# 2021_Deployment_REVB.net
KiCad netlist of a schematic drawn in EAGLE
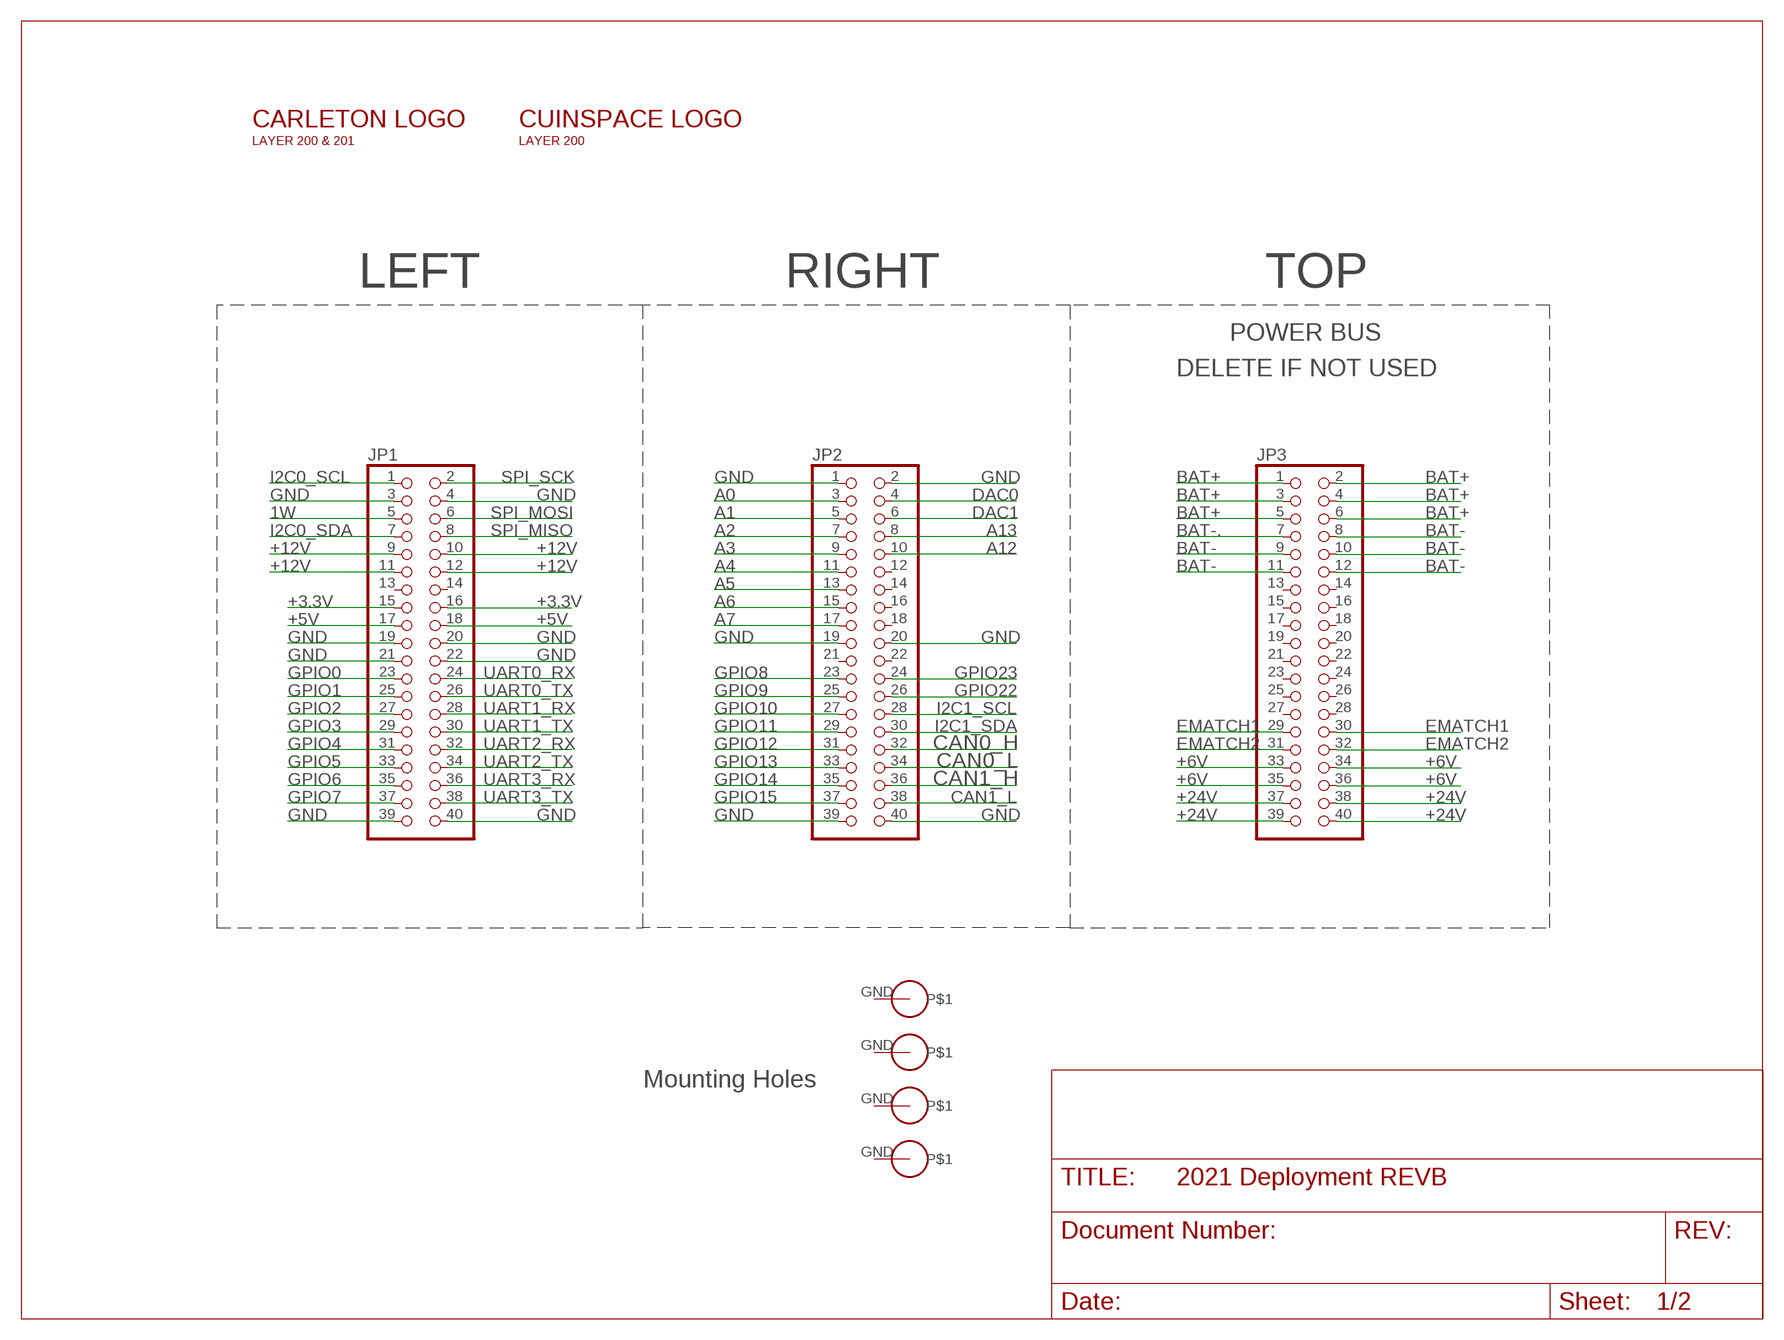
[diagram p0: schematic, sheet 1]
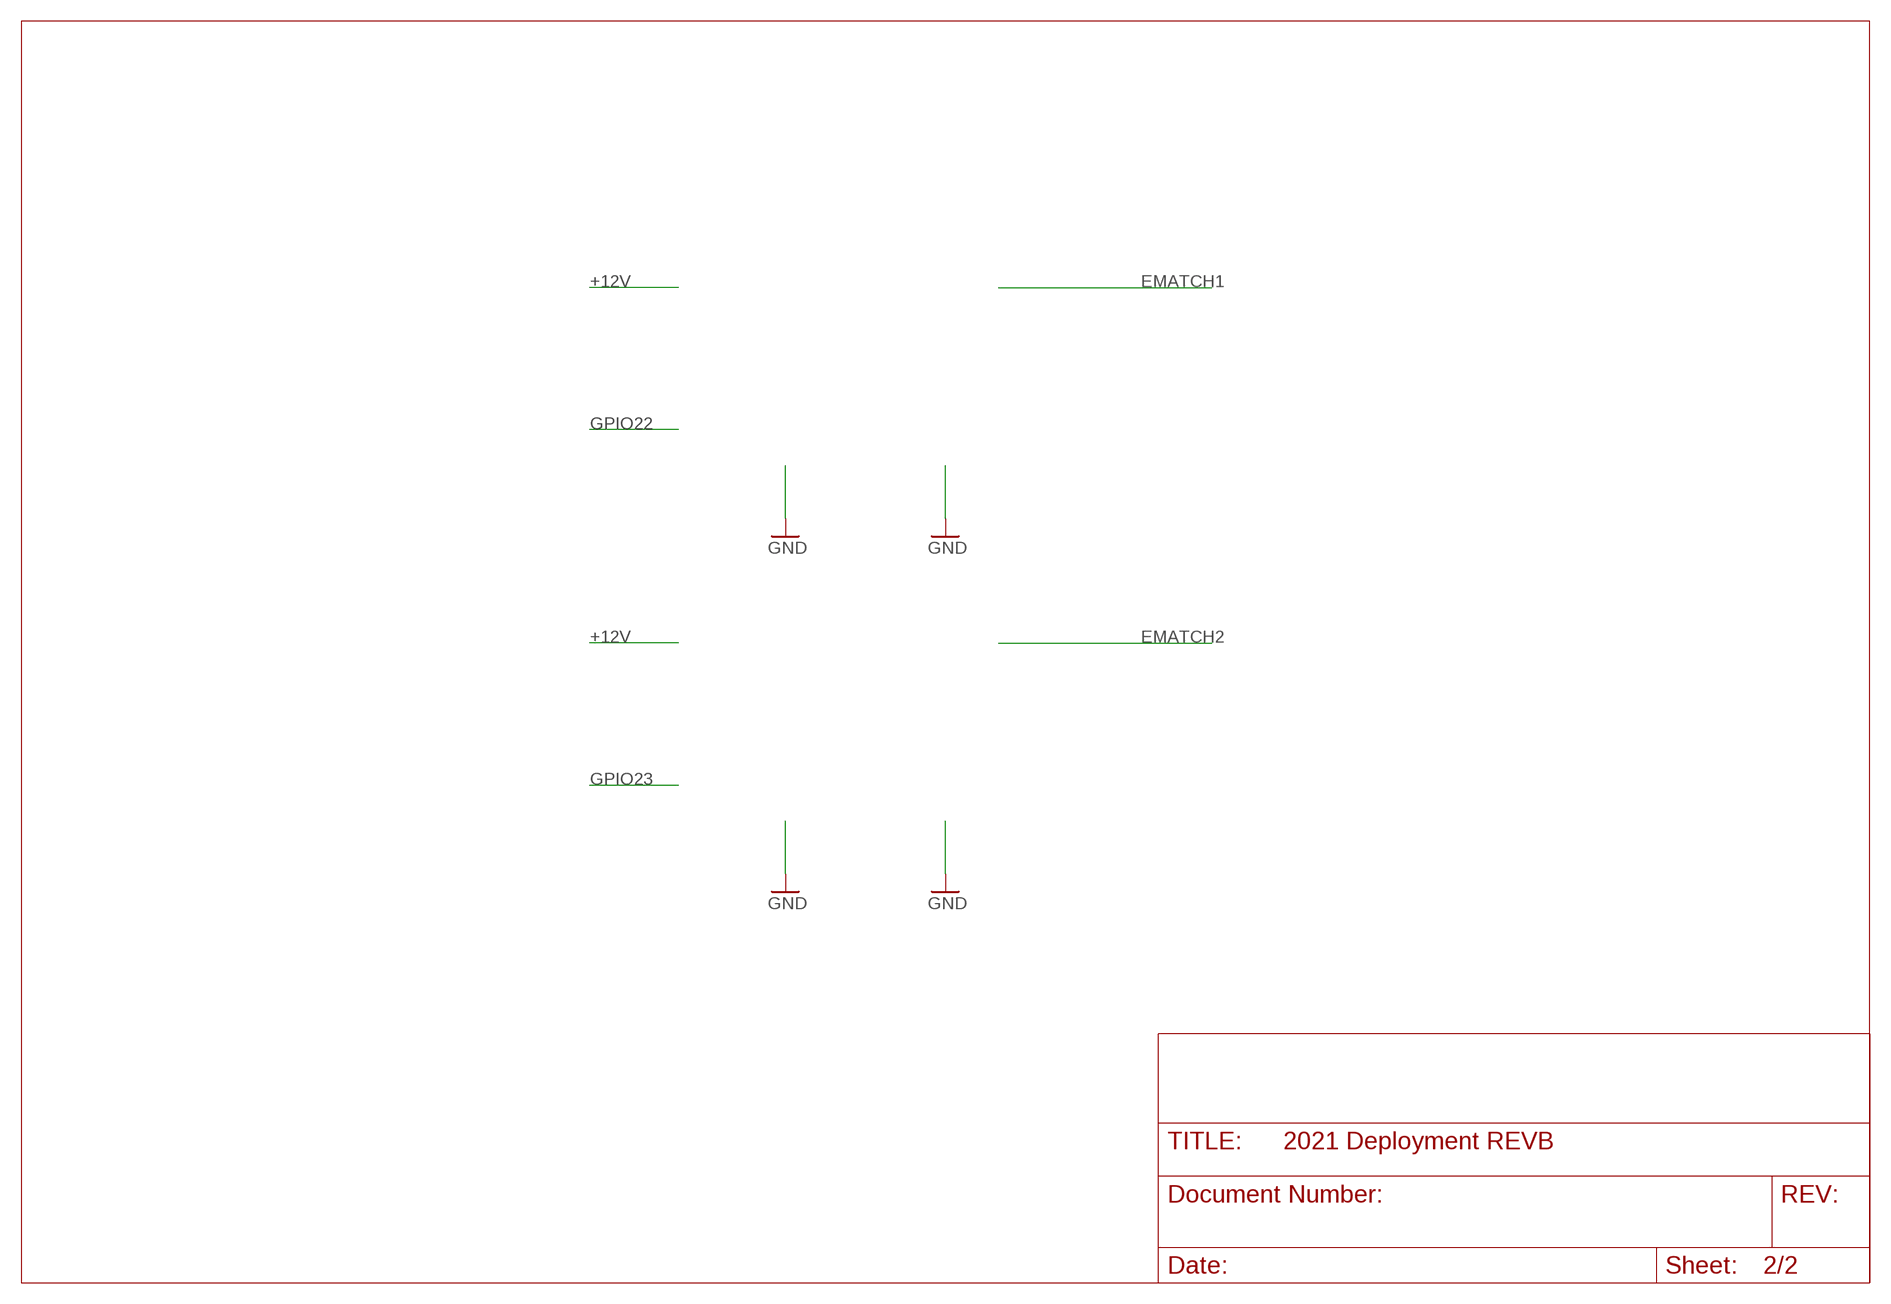
[diagram p1: schematic, sheet 2]

(export (version "E")
  (design (tool "Eeschema 10.0.6"))
  (components
    (comp (ref "$$U$1")
      (value "PS/104-MOUNTING-HOLE")
      (footprint "eagle-import:PC_104-MOUNTING-HOLE")
      (libsource (lib "eagle-import") (part "PS/104-MOUNTING-HOLE"))
    )
    (comp (ref "JP1")
      (value "PINHD-2X20")
      (footprint "eagle-import:2X20")
      (libsource (lib "eagle-import") (part "PINHD-2X20"))
    )
    (comp (ref "JP2")
      (value "PINHD-2X20")
      (footprint "eagle-import:2X20")
      (libsource (lib "eagle-import") (part "PINHD-2X20"))
    )
    (comp (ref "JP3")
      (value "PINHD-2X20")
      (footprint "eagle-import:2X20")
      (libsource (lib "eagle-import") (part "PINHD-2X20"))
    )
    (comp (ref "U$1")
      (value "PS/104-MOUNTING-HOLE")
      (footprint "eagle-import:PC_104-MOUNTING-HOLE")
      (libsource (lib "eagle-import") (part "PS/104-MOUNTING-HOLE"))
    )
    (comp (ref "U$2")
      (value "PS/104-MOUNTING-HOLE")
      (footprint "eagle-import:PC_104-MOUNTING-HOLE")
      (libsource (lib "eagle-import") (part "PS/104-MOUNTING-HOLE"))
    )
    (comp (ref "U$3")
      (value "PS/104-MOUNTING-HOLE")
      (footprint "eagle-import:PC_104-MOUNTING-HOLE")
      (libsource (lib "eagle-import") (part "PS/104-MOUNTING-HOLE"))
    )
    (comp (ref "U$4")
      (value "CARLETON3CM")
      (footprint "eagle-import:CARLETONU_3CM")
      (libsource (lib "eagle-import") (part "CARLETON3CM"))
    )
    (comp (ref "U$6")
      (value "INSPACE3CM_L")
      (footprint "eagle-import:INSPACE_3CM_LETTERS")
      (libsource (lib "eagle-import") (part "INSPACE3CM_L"))
    )
  )
  (nets
    (net (code "1") (name "+3.3V") (class "Default")
      (node (ref "JP1") (pin "15") (pinfunction "15_15") (pintype "passive"))
      (node (ref "JP1") (pin "16") (pinfunction "16_16") (pintype "passive"))
    )
    (net (code "2") (name "+5V") (class "Default")
      (node (ref "JP1") (pin "17") (pinfunction "17_17") (pintype "passive"))
      (node (ref "JP1") (pin "18") (pinfunction "18_18") (pintype "passive"))
    )
    (net (code "3") (name "+6V") (class "Default")
      (node (ref "JP3") (pin "33") (pinfunction "33_33") (pintype "passive"))
      (node (ref "JP3") (pin "34") (pinfunction "34_34") (pintype "passive"))
      (node (ref "JP3") (pin "35") (pinfunction "35_35") (pintype "passive"))
      (node (ref "JP3") (pin "36") (pinfunction "36_36") (pintype "passive"))
    )
    (net (code "4") (name "+12V") (class "Default")
      (node (ref "JP1") (pin "10") (pinfunction "10_10") (pintype "passive"))
      (node (ref "JP1") (pin "11") (pinfunction "11_11") (pintype "passive"))
      (node (ref "JP1") (pin "12") (pinfunction "12_12") (pintype "passive"))
      (node (ref "JP1") (pin "9") (pinfunction "9_9") (pintype "passive"))
    )
    (net (code "5") (name "+24V") (class "Default")
      (node (ref "JP3") (pin "37") (pinfunction "37_37") (pintype "passive"))
      (node (ref "JP3") (pin "38") (pinfunction "38_38") (pintype "passive"))
      (node (ref "JP3") (pin "39") (pinfunction "39_39") (pintype "passive"))
      (node (ref "JP3") (pin "40") (pinfunction "40_40") (pintype "passive"))
    )
    (net (code "6") (name "1W") (class "Default")
      (node (ref "JP1") (pin "5") (pinfunction "5_5") (pintype "passive"))
    )
    (net (code "7") (name "A0") (class "Default")
      (node (ref "JP2") (pin "3") (pinfunction "3_3") (pintype "passive"))
    )
    (net (code "8") (name "A1") (class "Default")
      (node (ref "JP2") (pin "5") (pinfunction "5_5") (pintype "passive"))
    )
    (net (code "9") (name "A2") (class "Default")
      (node (ref "JP2") (pin "7") (pinfunction "7_7") (pintype "passive"))
    )
    (net (code "10") (name "A3") (class "Default")
      (node (ref "JP2") (pin "9") (pinfunction "9_9") (pintype "passive"))
    )
    (net (code "11") (name "A4") (class "Default")
      (node (ref "JP2") (pin "11") (pinfunction "11_11") (pintype "passive"))
    )
    (net (code "12") (name "A5") (class "Default")
      (node (ref "JP2") (pin "13") (pinfunction "13_13") (pintype "passive"))
    )
    (net (code "13") (name "A6") (class "Default")
      (node (ref "JP2") (pin "15") (pinfunction "15_15") (pintype "passive"))
    )
    (net (code "14") (name "A7") (class "Default")
      (node (ref "JP2") (pin "17") (pinfunction "17_17") (pintype "passive"))
    )
    (net (code "15") (name "A12") (class "Default")
      (node (ref "JP2") (pin "10") (pinfunction "10_10") (pintype "passive"))
    )
    (net (code "16") (name "A13") (class "Default")
      (node (ref "JP2") (pin "8") (pinfunction "8_8") (pintype "passive"))
    )
    (net (code "17") (name "BAT+") (class "Default")
      (node (ref "JP3") (pin "1") (pinfunction "1_1") (pintype "passive"))
      (node (ref "JP3") (pin "2") (pinfunction "2_2") (pintype "passive"))
      (node (ref "JP3") (pin "3") (pinfunction "3_3") (pintype "passive"))
      (node (ref "JP3") (pin "4") (pinfunction "4_4") (pintype "passive"))
      (node (ref "JP3") (pin "5") (pinfunction "5_5") (pintype "passive"))
      (node (ref "JP3") (pin "6") (pinfunction "6_6") (pintype "passive"))
    )
    (net (code "18") (name "BAT-") (class "Default")
      (node (ref "JP3") (pin "10") (pinfunction "10_10") (pintype "passive"))
      (node (ref "JP3") (pin "11") (pinfunction "11_11") (pintype "passive"))
      (node (ref "JP3") (pin "12") (pinfunction "12_12") (pintype "passive"))
      (node (ref "JP3") (pin "8") (pinfunction "8_8") (pintype "passive"))
      (node (ref "JP3") (pin "9") (pinfunction "9_9") (pintype "passive"))
    )
    (net (code "19") (name "BAT-.") (class "Default")
      (node (ref "JP3") (pin "7") (pinfunction "7_7") (pintype "passive"))
    )
    (net (code "20") (name "CAN0_H") (class "Default")
      (node (ref "JP2") (pin "32") (pinfunction "32_32") (pintype "passive"))
    )
    (net (code "21") (name "CAN0_L") (class "Default")
      (node (ref "JP2") (pin "34") (pinfunction "34_34") (pintype "passive"))
    )
    (net (code "22") (name "CAN1_H") (class "Default")
      (node (ref "JP2") (pin "36") (pinfunction "36_36") (pintype "passive"))
    )
    (net (code "23") (name "CAN1_L") (class "Default")
      (node (ref "JP2") (pin "38") (pinfunction "38_38") (pintype "passive"))
    )
    (net (code "24") (name "DAC0") (class "Default")
      (node (ref "JP2") (pin "4") (pinfunction "4_4") (pintype "passive"))
    )
    (net (code "25") (name "DAC1") (class "Default")
      (node (ref "JP2") (pin "6") (pinfunction "6_6") (pintype "passive"))
    )
    (net (code "26") (name "EMATCH1") (class "Default")
      (node (ref "JP3") (pin "29") (pinfunction "29_29") (pintype "passive"))
      (node (ref "JP3") (pin "30") (pinfunction "30_30") (pintype "passive"))
    )
    (net (code "27") (name "EMATCH2") (class "Default")
      (node (ref "JP3") (pin "31") (pinfunction "31_31") (pintype "passive"))
      (node (ref "JP3") (pin "32") (pinfunction "32_32") (pintype "passive"))
    )
    (net (code "28") (name "GND") (class "Default")
      (node (ref "JP1") (pin "19") (pinfunction "19_19") (pintype "passive"))
      (node (ref "JP1") (pin "20") (pinfunction "20_20") (pintype "passive"))
      (node (ref "JP1") (pin "21") (pinfunction "21_21") (pintype "passive"))
      (node (ref "JP1") (pin "22") (pinfunction "22_22") (pintype "passive"))
      (node (ref "JP1") (pin "3") (pinfunction "3_3") (pintype "passive"))
      (node (ref "JP1") (pin "39") (pinfunction "39_39") (pintype "passive"))
      (node (ref "JP1") (pin "4") (pinfunction "4_4") (pintype "passive"))
      (node (ref "JP1") (pin "40") (pinfunction "40_40") (pintype "passive"))
      (node (ref "JP2") (pin "1") (pinfunction "1_1") (pintype "passive"))
      (node (ref "JP2") (pin "19") (pinfunction "19_19") (pintype "passive"))
      (node (ref "JP2") (pin "2") (pinfunction "2_2") (pintype "passive"))
      (node (ref "JP2") (pin "20") (pinfunction "20_20") (pintype "passive"))
      (node (ref "JP2") (pin "39") (pinfunction "39_39") (pintype "passive"))
      (node (ref "JP2") (pin "40") (pinfunction "40_40") (pintype "passive"))
    )
    (net (code "29") (name "GPIO0") (class "Default")
      (node (ref "JP1") (pin "23") (pinfunction "23_23") (pintype "passive"))
    )
    (net (code "30") (name "GPIO1") (class "Default")
      (node (ref "JP1") (pin "25") (pinfunction "25_25") (pintype "passive"))
    )
    (net (code "31") (name "GPIO2") (class "Default")
      (node (ref "JP1") (pin "27") (pinfunction "27_27") (pintype "passive"))
    )
    (net (code "32") (name "GPIO3") (class "Default")
      (node (ref "JP1") (pin "29") (pinfunction "29_29") (pintype "passive"))
    )
    (net (code "33") (name "GPIO4") (class "Default")
      (node (ref "JP1") (pin "31") (pinfunction "31_31") (pintype "passive"))
    )
    (net (code "34") (name "GPIO5") (class "Default")
      (node (ref "JP1") (pin "33") (pinfunction "33_33") (pintype "passive"))
    )
    (net (code "35") (name "GPIO6") (class "Default")
      (node (ref "JP1") (pin "35") (pinfunction "35_35") (pintype "passive"))
    )
    (net (code "36") (name "GPIO7") (class "Default")
      (node (ref "JP1") (pin "37") (pinfunction "37_37") (pintype "passive"))
    )
    (net (code "37") (name "GPIO8") (class "Default")
      (node (ref "JP2") (pin "23") (pinfunction "23_23") (pintype "passive"))
    )
    (net (code "38") (name "GPIO9") (class "Default")
      (node (ref "JP2") (pin "25") (pinfunction "25_25") (pintype "passive"))
    )
    (net (code "39") (name "GPIO10") (class "Default")
      (node (ref "JP2") (pin "27") (pinfunction "27_27") (pintype "passive"))
    )
    (net (code "40") (name "GPIO11") (class "Default")
      (node (ref "JP2") (pin "29") (pinfunction "29_29") (pintype "passive"))
    )
    (net (code "41") (name "GPIO12") (class "Default")
      (node (ref "JP2") (pin "31") (pinfunction "31_31") (pintype "passive"))
    )
    (net (code "42") (name "GPIO13") (class "Default")
      (node (ref "JP2") (pin "33") (pinfunction "33_33") (pintype "passive"))
    )
    (net (code "43") (name "GPIO14") (class "Default")
      (node (ref "JP2") (pin "35") (pinfunction "35_35") (pintype "passive"))
    )
    (net (code "44") (name "GPIO15") (class "Default")
      (node (ref "JP2") (pin "37") (pinfunction "37_37") (pintype "passive"))
    )
    (net (code "45") (name "GPIO22") (class "Default")
      (node (ref "JP2") (pin "26") (pinfunction "26_26") (pintype "passive"))
    )
    (net (code "46") (name "GPIO23") (class "Default")
      (node (ref "JP2") (pin "24") (pinfunction "24_24") (pintype "passive"))
    )
    (net (code "47") (name "I2C0_SCL") (class "Default")
      (node (ref "JP1") (pin "1") (pinfunction "1_1") (pintype "passive"))
    )
    (net (code "48") (name "I2C0_SDA") (class "Default")
      (node (ref "JP1") (pin "7") (pinfunction "7_7") (pintype "passive"))
    )
    (net (code "49") (name "I2C1_SCL") (class "Default")
      (node (ref "JP2") (pin "28") (pinfunction "28_28") (pintype "passive"))
    )
    (net (code "50") (name "I2C1_SDA") (class "Default")
      (node (ref "JP2") (pin "30") (pinfunction "30_30") (pintype "passive"))
    )
    (net (code "51") (name "SPI_MISO") (class "Default")
      (node (ref "JP1") (pin "8") (pinfunction "8_8") (pintype "passive"))
    )
    (net (code "52") (name "SPI_MOSI") (class "Default")
      (node (ref "JP1") (pin "6") (pinfunction "6_6") (pintype "passive"))
    )
    (net (code "53") (name "SPI_SCK") (class "Default")
      (node (ref "JP1") (pin "2") (pinfunction "2_2") (pintype "passive"))
    )
    (net (code "54") (name "UART0_RX") (class "Default")
      (node (ref "JP1") (pin "24") (pinfunction "24_24") (pintype "passive"))
    )
    (net (code "55") (name "UART0_TX") (class "Default")
      (node (ref "JP1") (pin "26") (pinfunction "26_26") (pintype "passive"))
    )
    (net (code "56") (name "UART1_RX") (class "Default")
      (node (ref "JP1") (pin "28") (pinfunction "28_28") (pintype "passive"))
    )
    (net (code "57") (name "UART1_TX") (class "Default")
      (node (ref "JP1") (pin "30") (pinfunction "30_30") (pintype "passive"))
    )
    (net (code "58") (name "UART2_RX") (class "Default")
      (node (ref "JP1") (pin "32") (pinfunction "32_32") (pintype "passive"))
    )
    (net (code "59") (name "UART2_TX") (class "Default")
      (node (ref "JP1") (pin "34") (pinfunction "34_34") (pintype "passive"))
    )
    (net (code "60") (name "UART3_RX") (class "Default")
      (node (ref "JP1") (pin "36") (pinfunction "36_36") (pintype "passive"))
    )
    (net (code "61") (name "UART3_TX") (class "Default")
      (node (ref "JP1") (pin "38") (pinfunction "38_38") (pintype "passive"))
    )
    (net (code "62") (name "unconnected-($$U$1-P$1-PadGND)") (class "Default")
      (node (ref "$$U$1") (pin "GND") (pinfunction "P$1_GND") (pintype "bidirectional"))
    )
    (net (code "63") (name "unconnected-(JP1-Pad13)") (class "Default")
      (node (ref "JP1") (pin "13") (pinfunction "13_13") (pintype "passive"))
    )
    (net (code "64") (name "unconnected-(JP1-Pad14)") (class "Default")
      (node (ref "JP1") (pin "14") (pinfunction "14_14") (pintype "passive"))
    )
    (net (code "65") (name "unconnected-(JP2-Pad12)") (class "Default")
      (node (ref "JP2") (pin "12") (pinfunction "12_12") (pintype "passive"))
    )
    (net (code "66") (name "unconnected-(JP2-Pad14)") (class "Default")
      (node (ref "JP2") (pin "14") (pinfunction "14_14") (pintype "passive"))
    )
    (net (code "67") (name "unconnected-(JP2-Pad16)") (class "Default")
      (node (ref "JP2") (pin "16") (pinfunction "16_16") (pintype "passive"))
    )
    (net (code "68") (name "unconnected-(JP2-Pad18)") (class "Default")
      (node (ref "JP2") (pin "18") (pinfunction "18_18") (pintype "passive"))
    )
    (net (code "69") (name "unconnected-(JP2-Pad21)") (class "Default")
      (node (ref "JP2") (pin "21") (pinfunction "21_21") (pintype "passive"))
    )
    (net (code "70") (name "unconnected-(JP2-Pad22)") (class "Default")
      (node (ref "JP2") (pin "22") (pinfunction "22_22") (pintype "passive"))
    )
    (net (code "71") (name "unconnected-(JP3-Pad13)") (class "Default")
      (node (ref "JP3") (pin "13") (pinfunction "13_13") (pintype "passive"))
    )
    (net (code "72") (name "unconnected-(JP3-Pad14)") (class "Default")
      (node (ref "JP3") (pin "14") (pinfunction "14_14") (pintype "passive"))
    )
    (net (code "73") (name "unconnected-(JP3-Pad15)") (class "Default")
      (node (ref "JP3") (pin "15") (pinfunction "15_15") (pintype "passive"))
    )
    (net (code "74") (name "unconnected-(JP3-Pad16)") (class "Default")
      (node (ref "JP3") (pin "16") (pinfunction "16_16") (pintype "passive"))
    )
    (net (code "75") (name "unconnected-(JP3-Pad17)") (class "Default")
      (node (ref "JP3") (pin "17") (pinfunction "17_17") (pintype "passive"))
    )
    (net (code "76") (name "unconnected-(JP3-Pad18)") (class "Default")
      (node (ref "JP3") (pin "18") (pinfunction "18_18") (pintype "passive"))
    )
    (net (code "77") (name "unconnected-(JP3-Pad19)") (class "Default")
      (node (ref "JP3") (pin "19") (pinfunction "19_19") (pintype "passive"))
    )
    (net (code "78") (name "unconnected-(JP3-Pad20)") (class "Default")
      (node (ref "JP3") (pin "20") (pinfunction "20_20") (pintype "passive"))
    )
    (net (code "79") (name "unconnected-(JP3-Pad21)") (class "Default")
      (node (ref "JP3") (pin "21") (pinfunction "21_21") (pintype "passive"))
    )
    (net (code "80") (name "unconnected-(JP3-Pad22)") (class "Default")
      (node (ref "JP3") (pin "22") (pinfunction "22_22") (pintype "passive"))
    )
    (net (code "81") (name "unconnected-(JP3-Pad23)") (class "Default")
      (node (ref "JP3") (pin "23") (pinfunction "23_23") (pintype "passive"))
    )
    (net (code "82") (name "unconnected-(JP3-Pad24)") (class "Default")
      (node (ref "JP3") (pin "24") (pinfunction "24_24") (pintype "passive"))
    )
    (net (code "83") (name "unconnected-(JP3-Pad25)") (class "Default")
      (node (ref "JP3") (pin "25") (pinfunction "25_25") (pintype "passive"))
    )
    (net (code "84") (name "unconnected-(JP3-Pad26)") (class "Default")
      (node (ref "JP3") (pin "26") (pinfunction "26_26") (pintype "passive"))
    )
    (net (code "85") (name "unconnected-(JP3-Pad27)") (class "Default")
      (node (ref "JP3") (pin "27") (pinfunction "27_27") (pintype "passive"))
    )
    (net (code "86") (name "unconnected-(JP3-Pad28)") (class "Default")
      (node (ref "JP3") (pin "28") (pinfunction "28_28") (pintype "passive"))
    )
    (net (code "87") (name "unconnected-(U$1-P$1-PadGND)") (class "Default")
      (node (ref "U$1") (pin "GND") (pinfunction "P$1_GND") (pintype "bidirectional"))
    )
    (net (code "88") (name "unconnected-(U$2-P$1-PadGND)") (class "Default")
      (node (ref "U$2") (pin "GND") (pinfunction "P$1_GND") (pintype "bidirectional"))
    )
    (net (code "89") (name "unconnected-(U$3-P$1-PadGND)") (class "Default")
      (node (ref "U$3") (pin "GND") (pinfunction "P$1_GND") (pintype "bidirectional"))
    )
  )
)
